# RTxManualControl.net
KiCad netlist of a schematic drawn in EAGLE
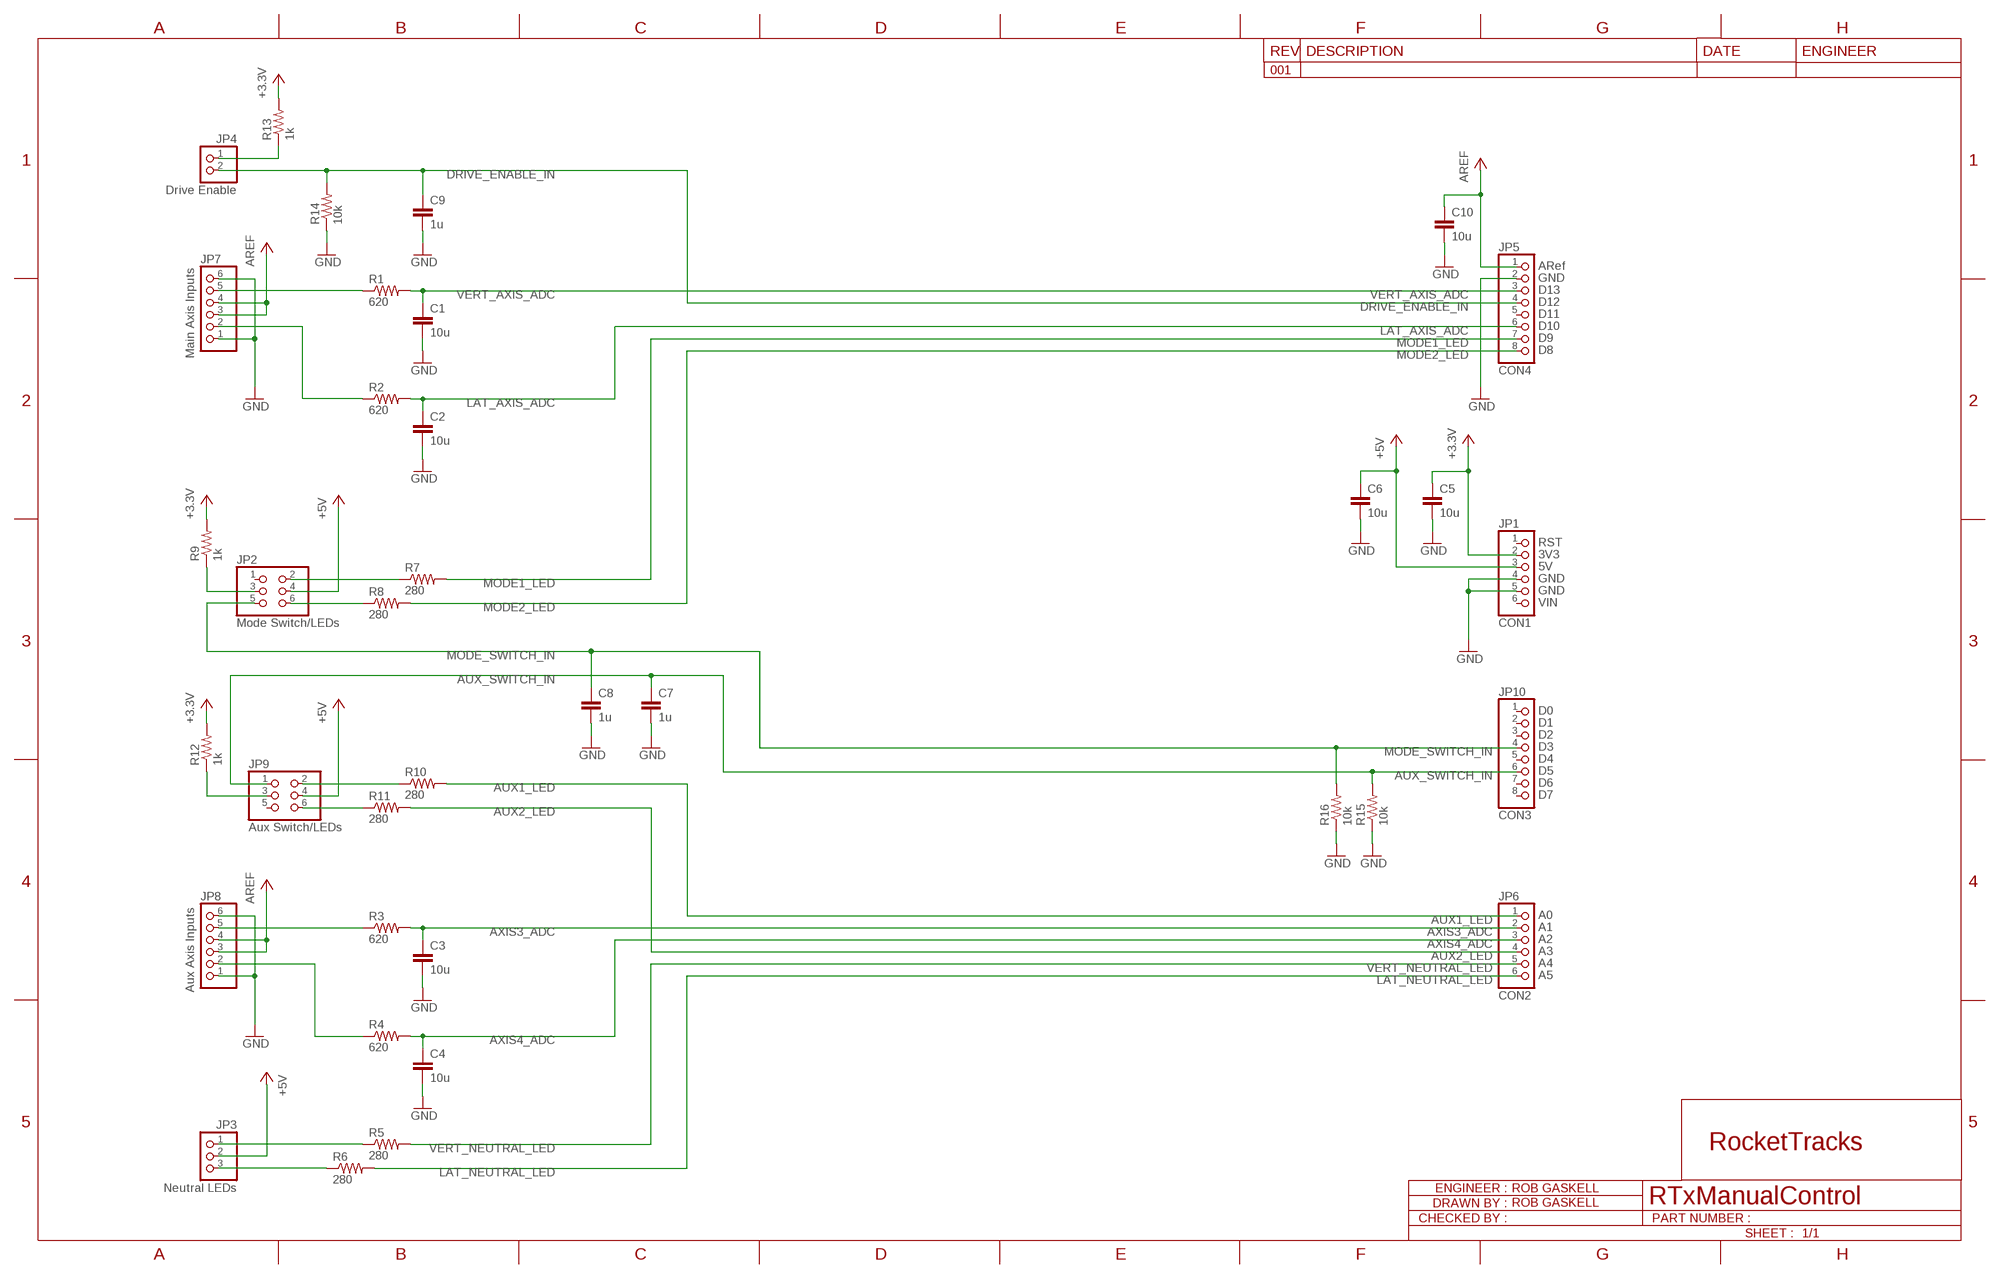
[diagram p0: schematic, sheet 1]

(export (version "E")
  (design (tool "Eeschema 10.0.6"))
  (components
    (comp (ref "C1")
      (value "10u")
      (footprint "eagle-import:C1206")
      (libsource (lib "eagle-import") (part "C-EUC1206"))
    )
    (comp (ref "C2")
      (value "10u")
      (footprint "eagle-import:C1206")
      (libsource (lib "eagle-import") (part "C-EUC1206"))
    )
    (comp (ref "C3")
      (value "10u")
      (footprint "eagle-import:C1206")
      (libsource (lib "eagle-import") (part "C-EUC1206"))
    )
    (comp (ref "C4")
      (value "10u")
      (footprint "eagle-import:C1206")
      (libsource (lib "eagle-import") (part "C-EUC1206"))
    )
    (comp (ref "C5")
      (value "10u")
      (footprint "eagle-import:C1206")
      (libsource (lib "eagle-import") (part "C-EUC1206"))
    )
    (comp (ref "C6")
      (value "10u")
      (footprint "eagle-import:C1206")
      (libsource (lib "eagle-import") (part "C-EUC1206"))
    )
    (comp (ref "C7")
      (value "1u")
      (footprint "eagle-import:C1206")
      (libsource (lib "eagle-import") (part "C-EUC1206"))
    )
    (comp (ref "C8")
      (value "1u")
      (footprint "eagle-import:C1206")
      (libsource (lib "eagle-import") (part "C-EUC1206"))
    )
    (comp (ref "C9")
      (value "1u")
      (footprint "eagle-import:C1206")
      (libsource (lib "eagle-import") (part "C-EUC1206"))
    )
    (comp (ref "C10")
      (value "10u")
      (footprint "eagle-import:C1206")
      (libsource (lib "eagle-import") (part "C-EUC1206"))
    )
    (comp (ref "JP1")
      (value "CON1")
      (footprint "eagle-import:1X06")
      (libsource (lib "eagle-import") (part "PINHD-1X6"))
    )
    (comp (ref "JP2")
      (value "Mode Switch/LEDs")
      (footprint "eagle-import:2X03")
      (libsource (lib "eagle-import") (part "PINHD-2X3"))
    )
    (comp (ref "JP3")
      (value "Neutral LEDs")
      (footprint "eagle-import:1X03")
      (libsource (lib "eagle-import") (part "PINHD-1X3"))
    )
    (comp (ref "JP4")
      (value "Drive Enable")
      (footprint "eagle-import:1X02")
      (libsource (lib "eagle-import") (part "PINHD-1X2"))
    )
    (comp (ref "JP5")
      (value "CON4")
      (footprint "eagle-import:1X08")
      (libsource (lib "eagle-import") (part "PINHD-1X8"))
    )
    (comp (ref "JP6")
      (value "CON2")
      (footprint "eagle-import:1X06")
      (libsource (lib "eagle-import") (part "PINHD-1X6"))
    )
    (comp (ref "JP7")
      (value "Main Axis Inputs")
      (footprint "eagle-import:1X06")
      (libsource (lib "eagle-import") (part "PINHD-1X6"))
    )
    (comp (ref "JP8")
      (value "Aux Axis Inputs")
      (footprint "eagle-import:1X06")
      (libsource (lib "eagle-import") (part "PINHD-1X6"))
    )
    (comp (ref "JP9")
      (value "Aux Switch/LEDs")
      (footprint "eagle-import:2X03")
      (libsource (lib "eagle-import") (part "PINHD-2X3"))
    )
    (comp (ref "JP10")
      (value "CON3")
      (footprint "eagle-import:1X08")
      (libsource (lib "eagle-import") (part "PINHD-1X8"))
    )
    (comp (ref "R1")
      (value "620")
      (footprint "eagle-import:R1206")
      (libsource (lib "eagle-import") (part "R-US_R1206"))
    )
    (comp (ref "R2")
      (value "620")
      (footprint "eagle-import:R1206")
      (libsource (lib "eagle-import") (part "R-US_R1206"))
    )
    (comp (ref "R3")
      (value "620")
      (footprint "eagle-import:R1206")
      (libsource (lib "eagle-import") (part "R-US_R1206"))
    )
    (comp (ref "R4")
      (value "620")
      (footprint "eagle-import:R1206")
      (libsource (lib "eagle-import") (part "R-US_R1206"))
    )
    (comp (ref "R5")
      (value "280")
      (footprint "eagle-import:R1206")
      (libsource (lib "eagle-import") (part "R-US_R1206"))
    )
    (comp (ref "R6")
      (value "280")
      (footprint "eagle-import:R1206")
      (libsource (lib "eagle-import") (part "R-US_R1206"))
    )
    (comp (ref "R7")
      (value "280")
      (footprint "eagle-import:R1206")
      (libsource (lib "eagle-import") (part "R-US_R1206"))
    )
    (comp (ref "R8")
      (value "280")
      (footprint "eagle-import:R1206")
      (libsource (lib "eagle-import") (part "R-US_R1206"))
    )
    (comp (ref "R9")
      (value "1k")
      (footprint "eagle-import:R1206")
      (libsource (lib "eagle-import") (part "R-US_R1206"))
    )
    (comp (ref "R10")
      (value "280")
      (footprint "eagle-import:R1206")
      (libsource (lib "eagle-import") (part "R-US_R1206"))
    )
    (comp (ref "R11")
      (value "280")
      (footprint "eagle-import:R1206")
      (libsource (lib "eagle-import") (part "R-US_R1206"))
    )
    (comp (ref "R12")
      (value "1k")
      (footprint "eagle-import:R1206")
      (libsource (lib "eagle-import") (part "R-US_R1206"))
    )
    (comp (ref "R13")
      (value "1k")
      (footprint "eagle-import:R1206")
      (libsource (lib "eagle-import") (part "R-US_R1206"))
    )
    (comp (ref "R14")
      (value "10k")
      (footprint "eagle-import:R1206")
      (libsource (lib "eagle-import") (part "R-US_R1206"))
    )
    (comp (ref "R15")
      (value "10k")
      (footprint "eagle-import:R1206")
      (libsource (lib "eagle-import") (part "R-US_R1206"))
    )
    (comp (ref "R16")
      (value "10k")
      (footprint "eagle-import:R1206")
      (libsource (lib "eagle-import") (part "R-US_R1206"))
    )
  )
  (nets
    (net (code "1") (name "+3.3V") (class "Default")
      (node (ref "C5") (pin "1") (pinfunction "1_1") (pintype "passive"))
      (node (ref "JP1") (pin "2") (pinfunction "2_2") (pintype "passive"))
      (node (ref "R12") (pin "2") (pinfunction "2_2") (pintype "passive"))
      (node (ref "R13") (pin "2") (pinfunction "2_2") (pintype "passive"))
      (node (ref "R9") (pin "2") (pinfunction "2_2") (pintype "passive"))
    )
    (net (code "2") (name "+5V") (class "Default")
      (node (ref "C6") (pin "1") (pinfunction "1_1") (pintype "passive"))
      (node (ref "JP1") (pin "3") (pinfunction "3_3") (pintype "passive"))
      (node (ref "JP2") (pin "4") (pinfunction "4_4") (pintype "passive"))
      (node (ref "JP3") (pin "2") (pinfunction "2_2") (pintype "passive"))
      (node (ref "JP9") (pin "4") (pinfunction "4_4") (pintype "passive"))
    )
    (net (code "3") (name "/AUX1_LED") (class "Default")
      (node (ref "JP6") (pin "1") (pinfunction "1_1") (pintype "passive"))
      (node (ref "R10") (pin "2") (pinfunction "2_2") (pintype "passive"))
    )
    (net (code "4") (name "/AUX2_LED") (class "Default")
      (node (ref "JP6") (pin "4") (pinfunction "4_4") (pintype "passive"))
      (node (ref "R11") (pin "2") (pinfunction "2_2") (pintype "passive"))
    )
    (net (code "5") (name "/AUX_SWITCH_IN") (class "Default")
      (node (ref "C7") (pin "1") (pinfunction "1_1") (pintype "passive"))
      (node (ref "JP10") (pin "6") (pinfunction "6_6") (pintype "passive"))
      (node (ref "JP9") (pin "1") (pinfunction "1_1") (pintype "passive"))
      (node (ref "R15") (pin "2") (pinfunction "2_2") (pintype "passive"))
    )
    (net (code "6") (name "/AXIS3_ADC") (class "Default")
      (node (ref "C3") (pin "1") (pinfunction "1_1") (pintype "passive"))
      (node (ref "JP6") (pin "2") (pinfunction "2_2") (pintype "passive"))
      (node (ref "R3") (pin "2") (pinfunction "2_2") (pintype "passive"))
    )
    (net (code "7") (name "/AXIS4_ADC") (class "Default")
      (node (ref "C4") (pin "1") (pinfunction "1_1") (pintype "passive"))
      (node (ref "JP6") (pin "3") (pinfunction "3_3") (pintype "passive"))
      (node (ref "R4") (pin "2") (pinfunction "2_2") (pintype "passive"))
    )
    (net (code "8") (name "/DRIVE_ENABLE_IN") (class "Default")
      (node (ref "C9") (pin "1") (pinfunction "1_1") (pintype "passive"))
      (node (ref "JP4") (pin "2") (pinfunction "2_2") (pintype "passive"))
      (node (ref "JP5") (pin "4") (pinfunction "4_4") (pintype "passive"))
      (node (ref "R14") (pin "2") (pinfunction "2_2") (pintype "passive"))
    )
    (net (code "9") (name "/LAT_AXIS_ADC") (class "Default")
      (node (ref "C2") (pin "1") (pinfunction "1_1") (pintype "passive"))
      (node (ref "JP5") (pin "6") (pinfunction "6_6") (pintype "passive"))
      (node (ref "R2") (pin "2") (pinfunction "2_2") (pintype "passive"))
    )
    (net (code "10") (name "/LAT_NEUTRAL_LED") (class "Default")
      (node (ref "JP6") (pin "6") (pinfunction "6_6") (pintype "passive"))
      (node (ref "R6") (pin "2") (pinfunction "2_2") (pintype "passive"))
    )
    (net (code "11") (name "/MODE1_LED") (class "Default")
      (node (ref "JP5") (pin "7") (pinfunction "7_7") (pintype "passive"))
      (node (ref "R7") (pin "2") (pinfunction "2_2") (pintype "passive"))
    )
    (net (code "12") (name "/MODE2_LED") (class "Default")
      (node (ref "JP5") (pin "8") (pinfunction "8_8") (pintype "passive"))
      (node (ref "R8") (pin "2") (pinfunction "2_2") (pintype "passive"))
    )
    (net (code "13") (name "/MODE_SWITCH_IN") (class "Default")
      (node (ref "C8") (pin "1") (pinfunction "1_1") (pintype "passive"))
      (node (ref "JP10") (pin "4") (pinfunction "4_4") (pintype "passive"))
      (node (ref "JP2") (pin "5") (pinfunction "5_5") (pintype "passive"))
      (node (ref "R16") (pin "2") (pinfunction "2_2") (pintype "passive"))
    )
    (net (code "14") (name "/VERT_AXIS_ADC") (class "Default")
      (node (ref "C1") (pin "1") (pinfunction "1_1") (pintype "passive"))
      (node (ref "JP5") (pin "3") (pinfunction "3_3") (pintype "passive"))
      (node (ref "R1") (pin "2") (pinfunction "2_2") (pintype "passive"))
    )
    (net (code "15") (name "/VERT_NEUTRAL_LED") (class "Default")
      (node (ref "JP6") (pin "5") (pinfunction "5_5") (pintype "passive"))
      (node (ref "R5") (pin "2") (pinfunction "2_2") (pintype "passive"))
    )
    (net (code "16") (name "AREF") (class "Default")
      (node (ref "C10") (pin "1") (pinfunction "1_1") (pintype "passive"))
      (node (ref "JP5") (pin "1") (pinfunction "1_1") (pintype "passive"))
      (node (ref "JP7") (pin "3") (pinfunction "3_3") (pintype "passive"))
      (node (ref "JP7") (pin "4") (pinfunction "4_4") (pintype "passive"))
      (node (ref "JP8") (pin "3") (pinfunction "3_3") (pintype "passive"))
      (node (ref "JP8") (pin "4") (pinfunction "4_4") (pintype "passive"))
    )
    (net (code "17") (name "GND") (class "Default")
      (node (ref "C1") (pin "2") (pinfunction "2_2") (pintype "passive"))
      (node (ref "C10") (pin "2") (pinfunction "2_2") (pintype "passive"))
      (node (ref "C2") (pin "2") (pinfunction "2_2") (pintype "passive"))
      (node (ref "C3") (pin "2") (pinfunction "2_2") (pintype "passive"))
      (node (ref "C4") (pin "2") (pinfunction "2_2") (pintype "passive"))
      (node (ref "C5") (pin "2") (pinfunction "2_2") (pintype "passive"))
      (node (ref "C6") (pin "2") (pinfunction "2_2") (pintype "passive"))
      (node (ref "C7") (pin "2") (pinfunction "2_2") (pintype "passive"))
      (node (ref "C8") (pin "2") (pinfunction "2_2") (pintype "passive"))
      (node (ref "C9") (pin "2") (pinfunction "2_2") (pintype "passive"))
      (node (ref "JP1") (pin "4") (pinfunction "4_4") (pintype "passive"))
      (node (ref "JP1") (pin "5") (pinfunction "5_5") (pintype "passive"))
      (node (ref "JP5") (pin "2") (pinfunction "2_2") (pintype "passive"))
      (node (ref "JP7") (pin "1") (pinfunction "1_1") (pintype "passive"))
      (node (ref "JP7") (pin "6") (pinfunction "6_6") (pintype "passive"))
      (node (ref "JP8") (pin "1") (pinfunction "1_1") (pintype "passive"))
      (node (ref "JP8") (pin "6") (pinfunction "6_6") (pintype "passive"))
      (node (ref "R14") (pin "1") (pinfunction "1_1") (pintype "passive"))
      (node (ref "R15") (pin "1") (pinfunction "1_1") (pintype "passive"))
      (node (ref "R16") (pin "1") (pinfunction "1_1") (pintype "passive"))
    )
    (net (code "18") (name "Net-(JP2-Pad2)") (class "Default")
      (node (ref "JP2") (pin "2") (pinfunction "2_2") (pintype "passive"))
      (node (ref "R7") (pin "1") (pinfunction "1_1") (pintype "passive"))
    )
    (net (code "19") (name "Net-(JP2-Pad3)") (class "Default")
      (node (ref "JP2") (pin "3") (pinfunction "3_3") (pintype "passive"))
      (node (ref "R9") (pin "1") (pinfunction "1_1") (pintype "passive"))
    )
    (net (code "20") (name "Net-(JP2-Pad6)") (class "Default")
      (node (ref "JP2") (pin "6") (pinfunction "6_6") (pintype "passive"))
      (node (ref "R8") (pin "1") (pinfunction "1_1") (pintype "passive"))
    )
    (net (code "21") (name "Net-(JP3-Pad1)") (class "Default")
      (node (ref "JP3") (pin "1") (pinfunction "1_1") (pintype "passive"))
      (node (ref "R5") (pin "1") (pinfunction "1_1") (pintype "passive"))
    )
    (net (code "22") (name "Net-(JP3-Pad3)") (class "Default")
      (node (ref "JP3") (pin "3") (pinfunction "3_3") (pintype "passive"))
      (node (ref "R6") (pin "1") (pinfunction "1_1") (pintype "passive"))
    )
    (net (code "23") (name "Net-(JP4-Pad1)") (class "Default")
      (node (ref "JP4") (pin "1") (pinfunction "1_1") (pintype "passive"))
      (node (ref "R13") (pin "1") (pinfunction "1_1") (pintype "passive"))
    )
    (net (code "24") (name "Net-(JP7-Pad2)") (class "Default")
      (node (ref "JP7") (pin "2") (pinfunction "2_2") (pintype "passive"))
      (node (ref "R2") (pin "1") (pinfunction "1_1") (pintype "passive"))
    )
    (net (code "25") (name "Net-(JP7-Pad5)") (class "Default")
      (node (ref "JP7") (pin "5") (pinfunction "5_5") (pintype "passive"))
      (node (ref "R1") (pin "1") (pinfunction "1_1") (pintype "passive"))
    )
    (net (code "26") (name "Net-(JP8-Pad2)") (class "Default")
      (node (ref "JP8") (pin "2") (pinfunction "2_2") (pintype "passive"))
      (node (ref "R4") (pin "1") (pinfunction "1_1") (pintype "passive"))
    )
    (net (code "27") (name "Net-(JP8-Pad5)") (class "Default")
      (node (ref "JP8") (pin "5") (pinfunction "5_5") (pintype "passive"))
      (node (ref "R3") (pin "1") (pinfunction "1_1") (pintype "passive"))
    )
    (net (code "28") (name "Net-(JP9-Pad2)") (class "Default")
      (node (ref "JP9") (pin "2") (pinfunction "2_2") (pintype "passive"))
      (node (ref "R10") (pin "1") (pinfunction "1_1") (pintype "passive"))
    )
    (net (code "29") (name "Net-(JP9-Pad3)") (class "Default")
      (node (ref "JP9") (pin "3") (pinfunction "3_3") (pintype "passive"))
      (node (ref "R12") (pin "1") (pinfunction "1_1") (pintype "passive"))
    )
    (net (code "30") (name "Net-(JP9-Pad6)") (class "Default")
      (node (ref "JP9") (pin "6") (pinfunction "6_6") (pintype "passive"))
      (node (ref "R11") (pin "1") (pinfunction "1_1") (pintype "passive"))
    )
    (net (code "31") (name "unconnected-(JP1-Pad1)") (class "Default")
      (node (ref "JP1") (pin "1") (pinfunction "1_1") (pintype "passive"))
    )
    (net (code "32") (name "unconnected-(JP1-Pad6)") (class "Default")
      (node (ref "JP1") (pin "6") (pinfunction "6_6") (pintype "passive"))
    )
    (net (code "33") (name "unconnected-(JP2-Pad1)") (class "Default")
      (node (ref "JP2") (pin "1") (pinfunction "1_1") (pintype "passive"))
    )
    (net (code "34") (name "unconnected-(JP5-Pad5)") (class "Default")
      (node (ref "JP5") (pin "5") (pinfunction "5_5") (pintype "passive"))
    )
    (net (code "35") (name "unconnected-(JP9-Pad5)") (class "Default")
      (node (ref "JP9") (pin "5") (pinfunction "5_5") (pintype "passive"))
    )
    (net (code "36") (name "unconnected-(JP10-Pad1)") (class "Default")
      (node (ref "JP10") (pin "1") (pinfunction "1_1") (pintype "passive"))
    )
    (net (code "37") (name "unconnected-(JP10-Pad2)") (class "Default")
      (node (ref "JP10") (pin "2") (pinfunction "2_2") (pintype "passive"))
    )
    (net (code "38") (name "unconnected-(JP10-Pad3)") (class "Default")
      (node (ref "JP10") (pin "3") (pinfunction "3_3") (pintype "passive"))
    )
    (net (code "39") (name "unconnected-(JP10-Pad5)") (class "Default")
      (node (ref "JP10") (pin "5") (pinfunction "5_5") (pintype "passive"))
    )
    (net (code "40") (name "unconnected-(JP10-Pad7)") (class "Default")
      (node (ref "JP10") (pin "7") (pinfunction "7_7") (pintype "passive"))
    )
    (net (code "41") (name "unconnected-(JP10-Pad8)") (class "Default")
      (node (ref "JP10") (pin "8") (pinfunction "8_8") (pintype "passive"))
    )
  )
)
